# XCVR.net
KiCad netlist of a schematic drawn in EAGLE
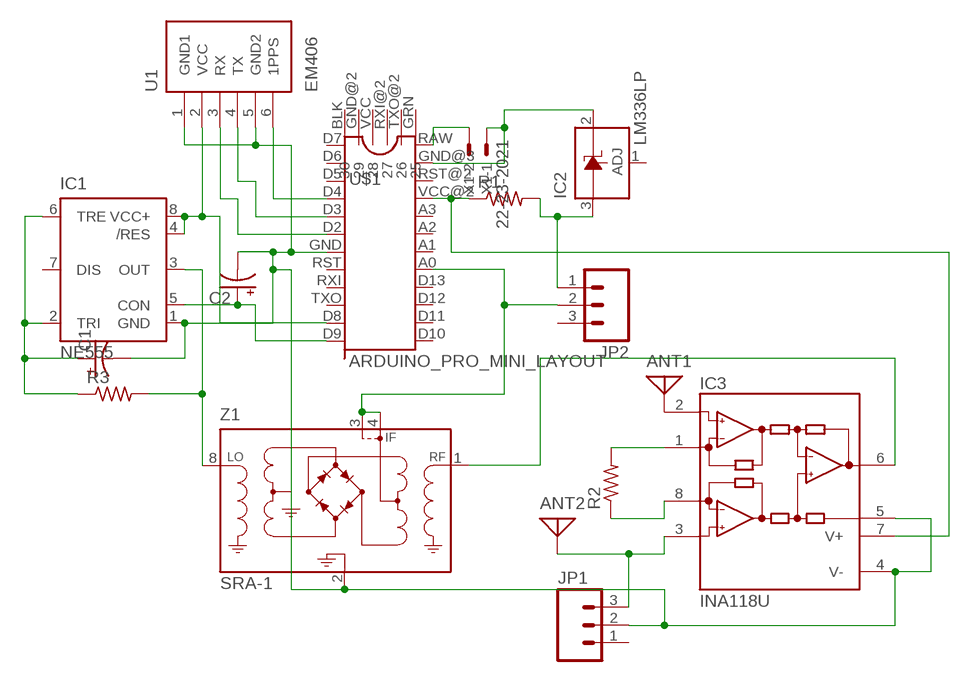
[diagram p0: schematic, sheet 1]

(export (version "E")
  (design (tool "Eeschema 10.0.6"))
  (components
    (comp (ref "ANT1")
      (value "ANTENNA")
      (footprint "eagle-import:PAD-01")
      (libsource (lib "eagle-import") (part "ANTENNA"))
    )
    (comp (ref "ANT2")
      (value "ANTENNA")
      (footprint "eagle-import:PAD-01")
      (libsource (lib "eagle-import") (part "ANTENNA"))
    )
    (comp (ref "C1")
      (value "CPOL-USE2,5-6E")
      (footprint "eagle-import:E2,5-6E")
      (libsource (lib "eagle-import") (part "CPOL-USE2,5-6E"))
    )
    (comp (ref "C2")
      (value "CPOL-USE2,5-6E")
      (footprint "eagle-import:E2,5-6E")
      (libsource (lib "eagle-import") (part "CPOL-USE2,5-6E"))
    )
    (comp (ref "IC1")
      (value "NE555")
      (footprint "eagle-import:DIL-08")
      (fields (field (name "MF") "Arrow Electronics") (field (name "MPN") "NE555N"))
      (libsource (lib "eagle-import") (part "NE555"))
    )
    (comp (ref "IC2")
      (value "LM336LP")
      (footprint "eagle-import:TO92")
      (libsource (lib "eagle-import") (part "LM336LP"))
    )
    (comp (ref "IC3")
      (value "INA118U")
      (footprint "eagle-import:SO08")
      (fields (field (name "MF") "TEXAS INSTRUMENTS"))
      (libsource (lib "eagle-import") (part "INA118U"))
    )
    (comp (ref "JP1")
      (value "M03PTH")
      (footprint "eagle-import:1X03")
      (libsource (lib "eagle-import") (part "M03PTH"))
    )
    (comp (ref "JP2")
      (value "M03PTH")
      (footprint "eagle-import:1X03")
      (libsource (lib "eagle-import") (part "M03PTH"))
    )
    (comp (ref "R1")
      (value "R-US_0204/5")
      (footprint "eagle-import:0204_5")
      (libsource (lib "eagle-import") (part "R-US_0204/5"))
    )
    (comp (ref "R2")
      (value "R-US_0204/5")
      (footprint "eagle-import:0204_5")
      (libsource (lib "eagle-import") (part "R-US_0204/5"))
    )
    (comp (ref "R3")
      (value "R-US_0204/5")
      (footprint "eagle-import:0204_5")
      (libsource (lib "eagle-import") (part "R-US_0204/5"))
    )
    (comp (ref "U$1")
      (value "ARDUINO_PRO_MINI_LAYOUT")
      (footprint "eagle-import:ARDUINO_PRO_MINI_PINOUT")
      (libsource (lib "eagle-import") (part "ARDUINO_PRO_MINI_LAYOUT"))
    )
    (comp (ref "U1")
      (value "EM406")
      (footprint "eagle-import:EM406")
      (libsource (lib "eagle-import") (part "EM406"))
    )
    (comp (ref "X1")
      (value "22-23-2021")
      (footprint "eagle-import:22-23-2021")
      (fields (field (name "MF") "MOLEX"))
      (libsource (lib "eagle-import") (part "22-23-2021"))
    )
    (comp (ref "Z1")
      (value "SRA-1")
      (footprint "eagle-import:A01")
      (libsource (lib "eagle-import") (part "SRA-1"))
    )
  )
  (nets
    (net (code "1") (name "Net-(IC1-CON)") (class "Default")
      (node (ref "C2") (pin "+") (pinfunction "+_+") (pintype "passive"))
      (node (ref "IC1") (pin "5") (pinfunction "CON_5") (pintype "input"))
      (node (ref "U$1") (pin "D9") (pinfunction "12_D9") (pintype "passive"))
    )
    (net (code "2") (name "Net-(IC1-GND)") (class "Default")
      (node (ref "C1") (pin "-") (pinfunction "-_-") (pintype "passive"))
      (node (ref "C2") (pin "-") (pinfunction "-_-") (pintype "passive"))
      (node (ref "IC1") (pin "1") (pinfunction "GND_1") (pintype "power_in"))
      (node (ref "IC3") (pin "4") (pinfunction "V-_4") (pintype "power_in"))
      (node (ref "IC3") (pin "5") (pinfunction "REF_5") (pintype "passive"))
      (node (ref "JP1") (pin "2") (pinfunction "2_2") (pintype "passive"))
      (node (ref "U$1") (pin "GND") (pinfunction "7_GND") (pintype "passive"))
      (node (ref "U1") (pin "1") (pinfunction "GND1_1") (pintype "bidirectional"))
      (node (ref "U1") (pin "5") (pinfunction "GND2_5") (pintype "bidirectional"))
      (node (ref "Z1") (pin "2") (pinfunction "CASEGROUND_2") (pintype "passive"))
    )
    (net (code "3") (name "Net-(IC1-OUT)") (class "Default")
      (node (ref "IC1") (pin "3") (pinfunction "OUT_3") (pintype "output"))
      (node (ref "R3") (pin "2") (pinfunction "2_2") (pintype "passive"))
      (node (ref "Z1") (pin "8") (pinfunction "L_8") (pintype "passive"))
    )
    (net (code "4") (name "Net-(IC1-TRE)") (class "Default")
      (node (ref "C1") (pin "+") (pinfunction "+_+") (pintype "passive"))
      (node (ref "IC1") (pin "2") (pinfunction "TRI_2") (pintype "input"))
      (node (ref "IC1") (pin "6") (pinfunction "TRE_6") (pintype "input"))
      (node (ref "R3") (pin "1") (pinfunction "1_1") (pintype "passive"))
    )
    (net (code "5") (name "Net-(IC1-VCC+)") (class "Default")
      (node (ref "IC1") (pin "4") (pinfunction "/RES_4") (pintype "input"))
      (node (ref "IC1") (pin "8") (pinfunction "VCC+_8") (pintype "power_in"))
      (node (ref "U$1") (pin "D8") (pinfunction "11_D8") (pintype "passive"))
      (node (ref "U1") (pin "2") (pinfunction "VCC_2") (pintype "bidirectional"))
    )
    (net (code "6") (name "Net-(IC2-A)") (class "Default")
      (node (ref "IC2") (pin "3") (pinfunction "A_3") (pintype "input"))
      (node (ref "JP2") (pin "1") (pinfunction "1_1") (pintype "passive"))
      (node (ref "R1") (pin "2") (pinfunction "2_2") (pintype "passive"))
    )
    (net (code "7") (name "Net-(IC2-C)") (class "Default")
      (node (ref "IC2") (pin "2") (pinfunction "C_2") (pintype "passive"))
      (node (ref "U$1") (pin "GND@3") (pinfunction "23_GND@3") (pintype "passive"))
      (node (ref "X1") (pin "1") (pinfunction "S_1") (pintype "passive"))
    )
    (net (code "8") (name "Net-(IC3-+IN)") (class "Default")
      (node (ref "ANT2") (pin "1") (pinfunction "1_1") (pintype "output"))
      (node (ref "IC3") (pin "3") (pinfunction "+IN_3") (pintype "input"))
      (node (ref "JP1") (pin "3") (pinfunction "3_3") (pintype "passive"))
    )
    (net (code "9") (name "Net-(IC3--IN)") (class "Default")
      (node (ref "ANT1") (pin "1") (pinfunction "1_1") (pintype "output"))
      (node (ref "IC3") (pin "2") (pinfunction "-IN_2") (pintype "input"))
    )
    (net (code "10") (name "Net-(IC3-OUT)") (class "Default")
      (node (ref "IC3") (pin "6") (pinfunction "OUT_6") (pintype "output"))
      (node (ref "Z1") (pin "1") (pinfunction "R_1") (pintype "passive"))
    )
    (net (code "11") (name "Net-(IC3-RG-Pad1)") (class "Default")
      (node (ref "IC3") (pin "1") (pinfunction "RG_1") (pintype "passive"))
      (node (ref "R2") (pin "2") (pinfunction "2_2") (pintype "passive"))
    )
    (net (code "12") (name "Net-(IC3-RG-Pad8)") (class "Default")
      (node (ref "IC3") (pin "8") (pinfunction "RG_8") (pintype "passive"))
      (node (ref "R2") (pin "1") (pinfunction "1_1") (pintype "passive"))
    )
    (net (code "13") (name "Net-(IC3-V+)") (class "Default")
      (node (ref "IC3") (pin "7") (pinfunction "V+_7") (pintype "power_in"))
      (node (ref "R1") (pin "1") (pinfunction "1_1") (pintype "passive"))
      (node (ref "U$1") (pin "VCC@2") (pinfunction "21_VCC@2") (pintype "passive"))
    )
    (net (code "14") (name "Net-(U$1-4)") (class "Default")
      (node (ref "U$1") (pin "D4") (pinfunction "4_D4") (pintype "passive"))
      (node (ref "U1") (pin "6") (pinfunction "1PPS_6") (pintype "bidirectional"))
    )
    (net (code "15") (name "Net-(U$1-5)") (class "Default")
      (node (ref "U$1") (pin "D3") (pinfunction "5_D3") (pintype "passive"))
      (node (ref "U1") (pin "4") (pinfunction "TX_4") (pintype "bidirectional"))
    )
    (net (code "16") (name "Net-(U$1-6)") (class "Default")
      (node (ref "U$1") (pin "D2") (pinfunction "6_D2") (pintype "passive"))
      (node (ref "U1") (pin "3") (pinfunction "RX_3") (pintype "bidirectional"))
    )
    (net (code "17") (name "Net-(U$1-17)") (class "Default")
      (node (ref "JP2") (pin "2") (pinfunction "2_2") (pintype "passive"))
      (node (ref "U$1") (pin "A0") (pinfunction "17_A0") (pintype "passive"))
      (node (ref "Z1") (pin "3") (pinfunction "IF_3") (pintype "passive"))
      (node (ref "Z1") (pin "4") (pinfunction "IF_4") (pintype "passive"))
    )
    (net (code "18") (name "Net-(U$1-24)") (class "Default")
      (node (ref "U$1") (pin "RAW") (pinfunction "24_RAW") (pintype "passive"))
      (node (ref "X1") (pin "2") (pinfunction "S_2") (pintype "passive"))
    )
    (net (code "19") (name "unconnected-(IC1-DIS-Pad7)") (class "Default")
      (node (ref "IC1") (pin "7") (pinfunction "DIS_7") (pintype "input"))
    )
    (net (code "20") (name "unconnected-(IC2-ADJ-Pad1)") (class "Default")
      (node (ref "IC2") (pin "1") (pinfunction "ADJ_1") (pintype "input"))
    )
    (net (code "21") (name "unconnected-(JP1-Pad1)") (class "Default")
      (node (ref "JP1") (pin "1") (pinfunction "1_1") (pintype "passive"))
    )
    (net (code "22") (name "unconnected-(JP2-Pad3)") (class "Default")
      (node (ref "JP2") (pin "3") (pinfunction "3_3") (pintype "passive"))
    )
    (net (code "23") (name "unconnected-(U$1-1-PadD7)") (class "Default")
      (node (ref "U$1") (pin "D7") (pinfunction "1_D7") (pintype "passive"))
    )
    (net (code "24") (name "unconnected-(U$1-2-PadD6)") (class "Default")
      (node (ref "U$1") (pin "D6") (pinfunction "2_D6") (pintype "passive"))
    )
    (net (code "25") (name "unconnected-(U$1-3-PadD5)") (class "Default")
      (node (ref "U$1") (pin "D5") (pinfunction "3_D5") (pintype "passive"))
    )
    (net (code "26") (name "unconnected-(U$1-8-PadRST)") (class "Default")
      (node (ref "U$1") (pin "RST") (pinfunction "8_RST") (pintype "passive"))
    )
    (net (code "27") (name "unconnected-(U$1-9-PadRXI)") (class "Default")
      (node (ref "U$1") (pin "RXI") (pinfunction "9_RXI") (pintype "passive"))
    )
    (net (code "28") (name "unconnected-(U$1-10-PadTXO)") (class "Default")
      (node (ref "U$1") (pin "TXO") (pinfunction "10_TXO") (pintype "passive"))
    )
    (net (code "29") (name "unconnected-(U$1-13-PadD10)") (class "Default")
      (node (ref "U$1") (pin "D10") (pinfunction "13_D10") (pintype "passive"))
    )
    (net (code "30") (name "unconnected-(U$1-14-PadD11)") (class "Default")
      (node (ref "U$1") (pin "D11") (pinfunction "14_D11") (pintype "passive"))
    )
    (net (code "31") (name "unconnected-(U$1-15-PadD12)") (class "Default")
      (node (ref "U$1") (pin "D12") (pinfunction "15_D12") (pintype "passive"))
    )
    (net (code "32") (name "unconnected-(U$1-16-PadD13)") (class "Default")
      (node (ref "U$1") (pin "D13") (pinfunction "16_D13") (pintype "passive"))
    )
    (net (code "33") (name "unconnected-(U$1-18-PadA1)") (class "Default")
      (node (ref "U$1") (pin "A1") (pinfunction "18_A1") (pintype "passive"))
    )
    (net (code "34") (name "unconnected-(U$1-19-PadA2)") (class "Default")
      (node (ref "U$1") (pin "A2") (pinfunction "19_A2") (pintype "passive"))
    )
    (net (code "35") (name "unconnected-(U$1-20-PadA3)") (class "Default")
      (node (ref "U$1") (pin "A3") (pinfunction "20_A3") (pintype "passive"))
    )
    (net (code "36") (name "unconnected-(U$1-22-PadRST@2)") (class "Default")
      (node (ref "U$1") (pin "RST@2") (pinfunction "22_RST@2") (pintype "passive"))
    )
    (net (code "37") (name "unconnected-(U$1-25-PadGRN)") (class "Default")
      (node (ref "U$1") (pin "GRN") (pinfunction "25_GRN") (pintype "bidirectional"))
    )
    (net (code "38") (name "unconnected-(U$1-26-PadTXO@2)") (class "Default")
      (node (ref "U$1") (pin "TXO@2") (pinfunction "26_TXO@2") (pintype "bidirectional"))
    )
    (net (code "39") (name "unconnected-(U$1-27-PadRXI@2)") (class "Default")
      (node (ref "U$1") (pin "RXI@2") (pinfunction "27_RXI@2") (pintype "bidirectional"))
    )
    (net (code "40") (name "unconnected-(U$1-28-PadVCC)") (class "Default")
      (node (ref "U$1") (pin "VCC") (pinfunction "28_VCC") (pintype "bidirectional"))
    )
    (net (code "41") (name "unconnected-(U$1-29-PadGND@2)") (class "Default")
      (node (ref "U$1") (pin "GND@2") (pinfunction "29_GND@2") (pintype "bidirectional"))
    )
    (net (code "42") (name "unconnected-(U$1-30-PadBLK)") (class "Default")
      (node (ref "U$1") (pin "BLK") (pinfunction "30_BLK") (pintype "bidirectional"))
    )
  )
)
